# SoftDrink-SchematicFile.net
KiCad netlist of a schematic drawn in EAGLE
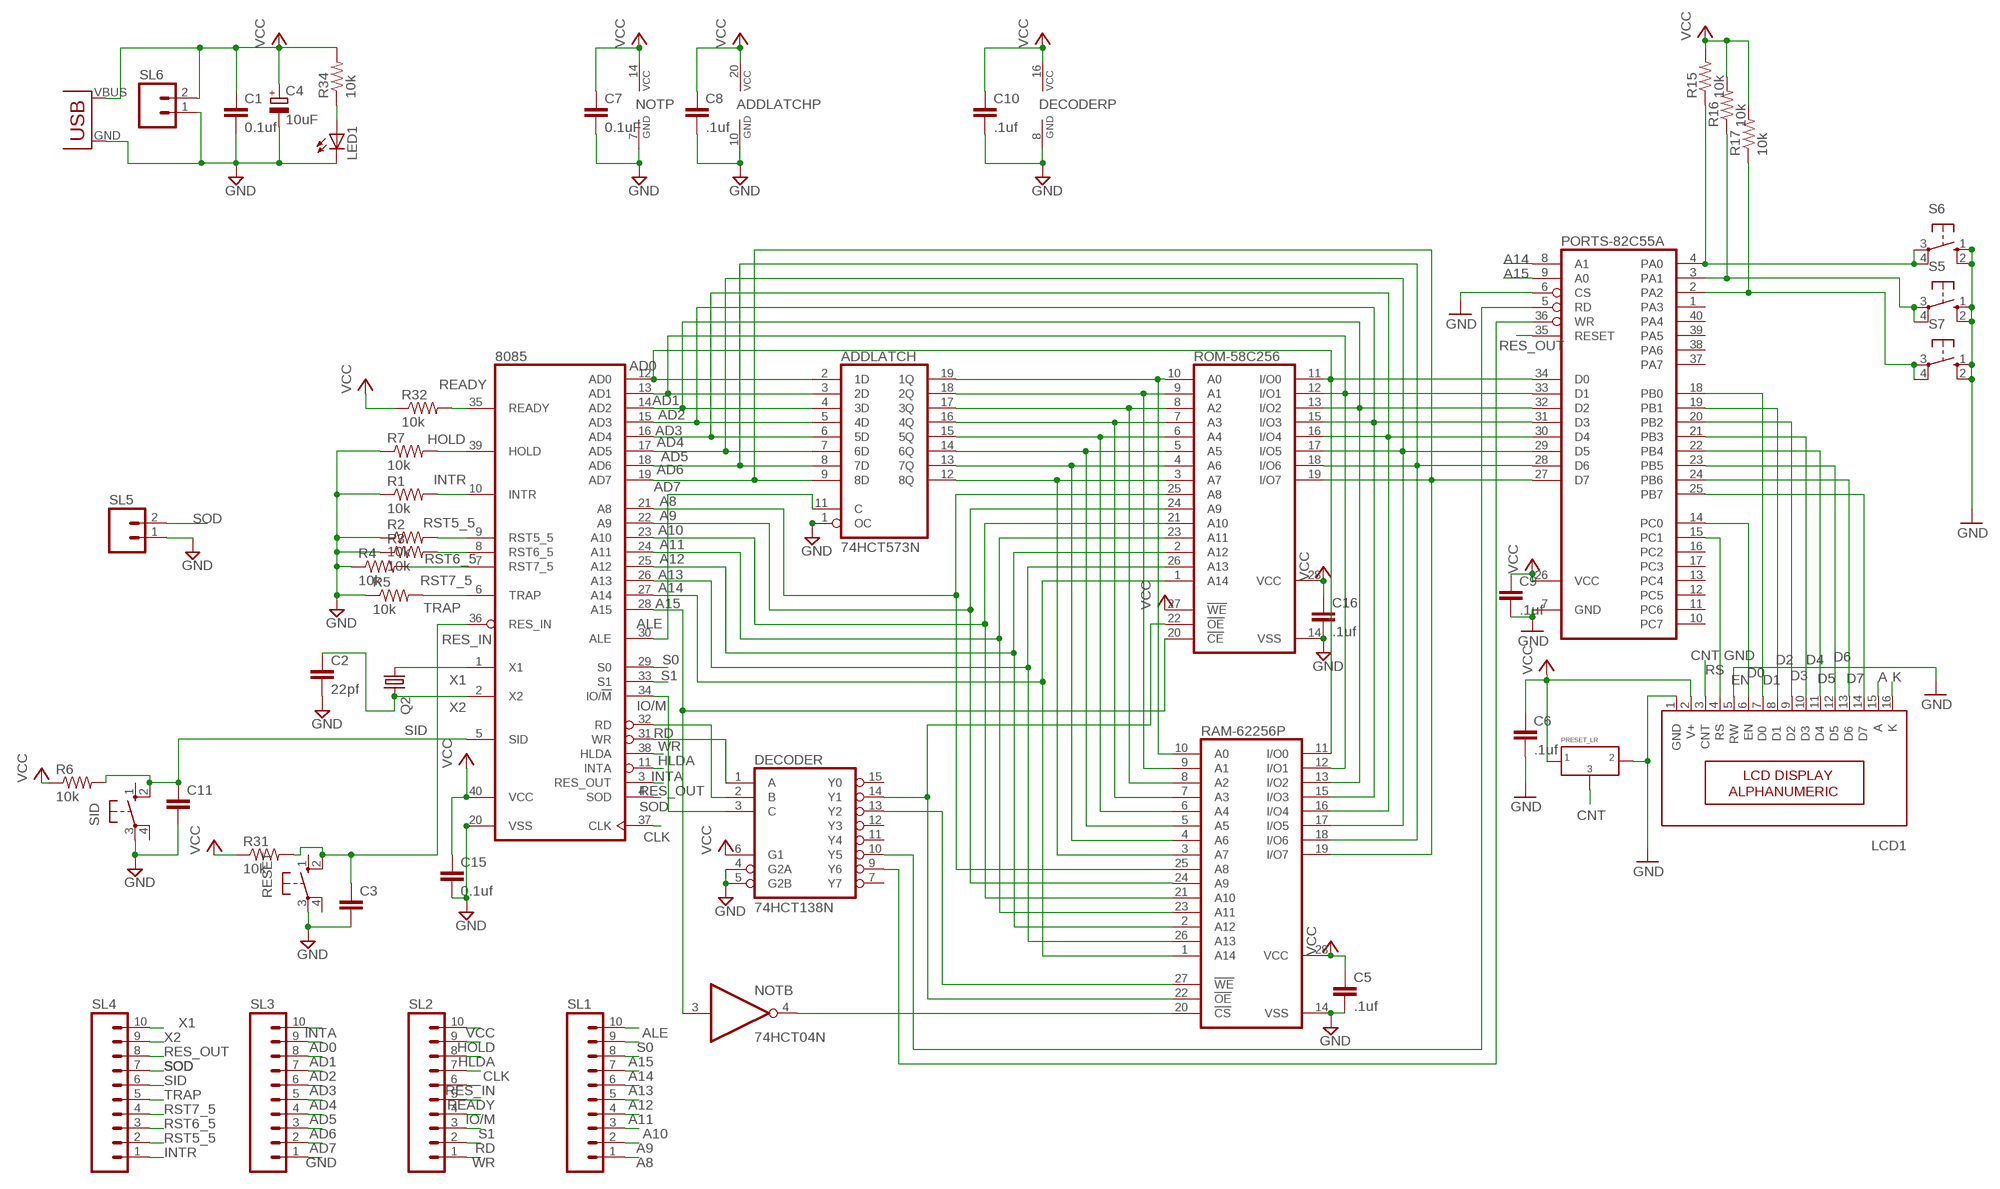
[diagram p0: schematic, sheet 1]

(export (version "E")
  (design (tool "Eeschema 10.0.6"))
  (components
    (comp (ref "8085")
      (value "8085")
      (footprint "eagle-import:DIL40")
      (libsource (lib "eagle-import") (part "8085"))
    )
    (comp (ref "ADDLATCH")
      (value "74HCT573N")
      (footprint "eagle-import:DIL20")
      (libsource (lib "eagle-import") (part "74573NHCT"))
    )
    (comp (ref "C1")
      (value "0.1uf")
      (footprint "eagle-import:C025-024X044")
      (libsource (lib "eagle-import") (part "C-EU025-024X044"))
    )
    (comp (ref "C2")
      (value "22pf")
      (footprint "eagle-import:C025-024X044")
      (libsource (lib "eagle-import") (part "C-EU025-024X044"))
    )
    (comp (ref "C3")
      (value "C-EU025-025X050")
      (footprint "eagle-import:C025-025X050")
      (libsource (lib "eagle-import") (part "C-EU025-025X050"))
    )
    (comp (ref "C4")
      (value "10uF")
      (footprint "eagle-import:E5-8,5")
      (libsource (lib "eagle-import") (part "CPOL-EUE5-8.5"))
    )
    (comp (ref "C5")
      (value ".1uf")
      (footprint "eagle-import:C025-024X044")
      (libsource (lib "eagle-import") (part "C-EU025-024X044"))
    )
    (comp (ref "C6")
      (value ".1uf")
      (footprint "eagle-import:C025-024X044")
      (libsource (lib "eagle-import") (part "C-EU025-024X044"))
    )
    (comp (ref "C7")
      (value "0.1uF")
      (footprint "eagle-import:C025-024X044")
      (libsource (lib "eagle-import") (part "C-EU025-024X044"))
    )
    (comp (ref "C8")
      (value ".1uf")
      (footprint "eagle-import:C025-024X044")
      (libsource (lib "eagle-import") (part "C-EU025-024X044"))
    )
    (comp (ref "C9")
      (value ".1uf")
      (footprint "eagle-import:C025-024X044")
      (libsource (lib "eagle-import") (part "C-EU025-024X044"))
    )
    (comp (ref "C10")
      (value ".1uf")
      (footprint "eagle-import:C025-024X044")
      (libsource (lib "eagle-import") (part "C-EU025-024X044"))
    )
    (comp (ref "C11")
      (value "C-EU025-025X050")
      (footprint "eagle-import:C025-025X050")
      (libsource (lib "eagle-import") (part "C-EU025-025X050"))
    )
    (comp (ref "C15")
      (value "0.1uf")
      (footprint "eagle-import:C025-024X044")
      (libsource (lib "eagle-import") (part "C-EU025-024X044"))
    )
    (comp (ref "C16")
      (value ".1uf")
      (footprint "eagle-import:C025-024X044")
      (libsource (lib "eagle-import") (part "C-EU025-024X044"))
    )
    (comp (ref "DECODER")
      (value "74HCT138N")
      (footprint "eagle-import:DIL16")
      (libsource (lib "eagle-import") (part "74138NHCT"))
    )
    (comp (ref "LCD1")
      (value "16X2LCD")
      (footprint "eagle-import:16X2_LCD")
      (libsource (lib "eagle-import") (part "16X2LCD"))
    )
    (comp (ref "LED1")
      (value "LED5MM")
      (footprint "eagle-import:LED5MM")
      (libsource (lib "eagle-import") (part "LED5MM"))
    )
    (comp (ref "NOT")
      (value "74HCT04N")
      (footprint "eagle-import:DIL14")
      (libsource (lib "eagle-import") (part "7404NHCT"))
    )
    (comp (ref "PORTS-82C55A")
      (value "82C55A")
      (footprint "eagle-import:DIL40")
      (fields (field (name "MF") "INTERSIL") (field (name "MPN") "IP82C55AZ"))
      (libsource (lib "eagle-import") (part "82C55A"))
    )
    (comp (ref "Q2")
      (value "CRYSTALHC49US")
      (footprint "eagle-import:HC49US")
      (libsource (lib "eagle-import") (part "CRYSTALHC49US"))
    )
    (comp (ref "R1")
      (value "10k")
      (footprint "eagle-import:0207_7")
      (libsource (lib "eagle-import") (part "R-US_0207/7"))
    )
    (comp (ref "R2")
      (value "10k")
      (footprint "eagle-import:0207_7")
      (libsource (lib "eagle-import") (part "R-US_0207/7"))
    )
    (comp (ref "R3")
      (value "10k")
      (footprint "eagle-import:0207_7")
      (libsource (lib "eagle-import") (part "R-US_0207/7"))
    )
    (comp (ref "R4")
      (value "10k")
      (footprint "eagle-import:0207_7")
      (libsource (lib "eagle-import") (part "R-US_0207/7"))
    )
    (comp (ref "R5")
      (value "10k")
      (footprint "eagle-import:0207_7")
      (libsource (lib "eagle-import") (part "R-US_0207/7"))
    )
    (comp (ref "R6")
      (value "10k")
      (footprint "eagle-import:0207_7")
      (libsource (lib "eagle-import") (part "R-US_0207/7"))
    )
    (comp (ref "R7")
      (value "10k")
      (footprint "eagle-import:0207_7")
      (libsource (lib "eagle-import") (part "R-US_0207/7"))
    )
    (comp (ref "R15")
      (value "10k")
      (footprint "eagle-import:0207_7")
      (libsource (lib "eagle-import") (part "R-US_0207/7"))
    )
    (comp (ref "R16")
      (value "10k")
      (footprint "eagle-import:0207_7")
      (libsource (lib "eagle-import") (part "R-US_0207/7"))
    )
    (comp (ref "R17")
      (value "10k")
      (footprint "eagle-import:0207_7")
      (libsource (lib "eagle-import") (part "R-US_0207/7"))
    )
    (comp (ref "R31")
      (value "10k")
      (footprint "eagle-import:0207_7")
      (libsource (lib "eagle-import") (part "R-US_0207/7"))
    )
    (comp (ref "R32")
      (value "10k")
      (footprint "eagle-import:0207_7")
      (libsource (lib "eagle-import") (part "R-US_0207/7"))
    )
    (comp (ref "R34")
      (value "10k")
      (footprint "eagle-import:0207_7")
      (libsource (lib "eagle-import") (part "R-US_0207/7"))
    )
    (comp (ref "RAM-62256P")
      (value "62256P")
      (footprint "eagle-import:DIL28-6")
      (libsource (lib "eagle-import") (part "62256P"))
    )
    (comp (ref "RESET")
      (value "10-XX")
      (footprint "eagle-import:B3F-10XX")
      (libsource (lib "eagle-import") (part "10-XX"))
    )
    (comp (ref "ROM-58C256")
      (value "58C256P")
      (footprint "eagle-import:DIL28-6")
      (fields (field (name "MPN") "HN58C256AP85E"))
      (libsource (lib "eagle-import") (part "58C256P"))
    )
    (comp (ref "S5")
      (value "10-XX")
      (footprint "eagle-import:B3F-10XX")
      (libsource (lib "eagle-import") (part "CEDTv79_10-XX"))
    )
    (comp (ref "S6")
      (value "10-XX")
      (footprint "eagle-import:B3F-10XX")
      (libsource (lib "eagle-import") (part "CEDTv79_10-XX"))
    )
    (comp (ref "S7")
      (value "10-XX")
      (footprint "eagle-import:B3F-10XX")
      (libsource (lib "eagle-import") (part "CEDTv79_10-XX"))
    )
    (comp (ref "SID")
      (value "10-XX")
      (footprint "eagle-import:B3F-10XX")
      (libsource (lib "eagle-import") (part "10-XX"))
    )
    (comp (ref "SL1")
      (value "M10")
      (footprint "eagle-import:10P")
      (libsource (lib "eagle-import") (part "M10"))
    )
    (comp (ref "SL2")
      (value "M10")
      (footprint "eagle-import:10P")
      (libsource (lib "eagle-import") (part "M10"))
    )
    (comp (ref "SL3")
      (value "M10")
      (footprint "eagle-import:10P")
      (libsource (lib "eagle-import") (part "M10"))
    )
    (comp (ref "SL4")
      (value "M10")
      (footprint "eagle-import:10P")
      (libsource (lib "eagle-import") (part "M10"))
    )
    (comp (ref "SL5")
      (value "M02")
      (footprint "eagle-import:02P")
      (libsource (lib "eagle-import") (part "M02"))
    )
    (comp (ref "SL6")
      (value "M02")
      (footprint "eagle-import:02P")
      (libsource (lib "eagle-import") (part "M02"))
    )
    (comp (ref "U$2")
      (value "USB(POWER)")
      (footprint "eagle-import:USB(POWER)")
      (libsource (lib "eagle-import") (part "USB(POWER)"))
    )
    (comp (ref "U$3")
      (value "PRESET_LR")
      (footprint "eagle-import:PRESET_LR")
      (libsource (lib "eagle-import") (part "PRESET_LR"))
    )
  )
  (nets
    (net (code "1") (name "/A") (class "Default")
      (node (ref "LCD1") (pin "15") (pinfunction "A_15") (pintype "bidirectional"))
    )
    (net (code "2") (name "/A8") (class "Default")
      (node (ref "8085") (pin "21") (pinfunction "A8_21") (pintype "output"))
      (node (ref "RAM-62256P") (pin "25") (pinfunction "A8_25") (pintype "input"))
      (node (ref "ROM-58C256") (pin "25") (pinfunction "A8_25") (pintype "input"))
      (node (ref "SL1") (pin "1") (pinfunction "1_1") (pintype "passive"))
    )
    (net (code "3") (name "/A9") (class "Default")
      (node (ref "8085") (pin "22") (pinfunction "A9_22") (pintype "output"))
      (node (ref "RAM-62256P") (pin "24") (pinfunction "A9_24") (pintype "input"))
      (node (ref "ROM-58C256") (pin "24") (pinfunction "A9_24") (pintype "input"))
      (node (ref "SL1") (pin "2") (pinfunction "2_2") (pintype "passive"))
    )
    (net (code "4") (name "/A10") (class "Default")
      (node (ref "8085") (pin "23") (pinfunction "A10_23") (pintype "output"))
      (node (ref "RAM-62256P") (pin "21") (pinfunction "A10_21") (pintype "input"))
      (node (ref "ROM-58C256") (pin "21") (pinfunction "A10_21") (pintype "input"))
      (node (ref "SL1") (pin "3") (pinfunction "3_3") (pintype "passive"))
    )
    (net (code "5") (name "/A11") (class "Default")
      (node (ref "8085") (pin "24") (pinfunction "A11_24") (pintype "output"))
      (node (ref "RAM-62256P") (pin "23") (pinfunction "A11_23") (pintype "input"))
      (node (ref "ROM-58C256") (pin "23") (pinfunction "A11_23") (pintype "input"))
      (node (ref "SL1") (pin "4") (pinfunction "4_4") (pintype "passive"))
    )
    (net (code "6") (name "/A12") (class "Default")
      (node (ref "8085") (pin "25") (pinfunction "A12_25") (pintype "output"))
      (node (ref "RAM-62256P") (pin "2") (pinfunction "A12_2") (pintype "input"))
      (node (ref "ROM-58C256") (pin "2") (pinfunction "A12_2") (pintype "input"))
      (node (ref "SL1") (pin "5") (pinfunction "5_5") (pintype "passive"))
    )
    (net (code "7") (name "/A13") (class "Default")
      (node (ref "8085") (pin "26") (pinfunction "A13_26") (pintype "output"))
      (node (ref "RAM-62256P") (pin "26") (pinfunction "A13_26") (pintype "input"))
      (node (ref "ROM-58C256") (pin "26") (pinfunction "A13_26") (pintype "input"))
      (node (ref "SL1") (pin "6") (pinfunction "6_6") (pintype "passive"))
    )
    (net (code "8") (name "/A14") (class "Default")
      (node (ref "8085") (pin "27") (pinfunction "A14_27") (pintype "output"))
      (node (ref "PORTS-82C55A") (pin "8") (pinfunction "A1_8") (pintype "input"))
      (node (ref "RAM-62256P") (pin "1") (pinfunction "A14_1") (pintype "input"))
      (node (ref "ROM-58C256") (pin "1") (pinfunction "A14_1") (pintype "input"))
      (node (ref "SL1") (pin "7") (pinfunction "7_7") (pintype "passive"))
    )
    (net (code "9") (name "/A15") (class "Default")
      (node (ref "8085") (pin "28") (pinfunction "A15_28") (pintype "output"))
      (node (ref "NOT") (pin "3") (pinfunction "I_3") (pintype "input"))
      (node (ref "PORTS-82C55A") (pin "9") (pinfunction "A0_9") (pintype "input"))
      (node (ref "ROM-58C256") (pin "20") (pinfunction "~{CE}_20") (pintype "input"))
      (node (ref "SL1") (pin "8") (pinfunction "8_8") (pintype "passive"))
    )
    (net (code "10") (name "/AD0") (class "Default")
      (node (ref "8085") (pin "12") (pinfunction "AD0_12") (pintype "bidirectional"))
      (node (ref "ADDLATCH") (pin "2") (pinfunction "1D_2") (pintype "input"))
      (node (ref "PORTS-82C55A") (pin "34") (pinfunction "D0_34") (pintype "bidirectional"))
      (node (ref "RAM-62256P") (pin "11") (pinfunction "I/O0_11") (pintype "bidirectional"))
      (node (ref "ROM-58C256") (pin "11") (pinfunction "I/O0_11") (pintype "tri_state"))
      (node (ref "SL3") (pin "9") (pinfunction "9_9") (pintype "passive"))
    )
    (net (code "11") (name "/AD1") (class "Default")
      (node (ref "8085") (pin "13") (pinfunction "AD1_13") (pintype "bidirectional"))
      (node (ref "ADDLATCH") (pin "3") (pinfunction "2D_3") (pintype "input"))
      (node (ref "PORTS-82C55A") (pin "33") (pinfunction "D1_33") (pintype "bidirectional"))
      (node (ref "RAM-62256P") (pin "12") (pinfunction "I/O1_12") (pintype "bidirectional"))
      (node (ref "ROM-58C256") (pin "12") (pinfunction "I/O1_12") (pintype "tri_state"))
      (node (ref "SL3") (pin "8") (pinfunction "8_8") (pintype "passive"))
    )
    (net (code "12") (name "/AD2") (class "Default")
      (node (ref "8085") (pin "14") (pinfunction "AD2_14") (pintype "bidirectional"))
      (node (ref "ADDLATCH") (pin "4") (pinfunction "3D_4") (pintype "input"))
      (node (ref "PORTS-82C55A") (pin "32") (pinfunction "D2_32") (pintype "bidirectional"))
      (node (ref "RAM-62256P") (pin "13") (pinfunction "I/O2_13") (pintype "bidirectional"))
      (node (ref "ROM-58C256") (pin "13") (pinfunction "I/O2_13") (pintype "tri_state"))
      (node (ref "SL3") (pin "7") (pinfunction "7_7") (pintype "passive"))
    )
    (net (code "13") (name "/AD3") (class "Default")
      (node (ref "8085") (pin "15") (pinfunction "AD3_15") (pintype "bidirectional"))
      (node (ref "ADDLATCH") (pin "5") (pinfunction "4D_5") (pintype "input"))
      (node (ref "PORTS-82C55A") (pin "31") (pinfunction "D3_31") (pintype "bidirectional"))
      (node (ref "RAM-62256P") (pin "15") (pinfunction "I/O3_15") (pintype "bidirectional"))
      (node (ref "ROM-58C256") (pin "15") (pinfunction "I/O3_15") (pintype "tri_state"))
      (node (ref "SL3") (pin "6") (pinfunction "6_6") (pintype "passive"))
    )
    (net (code "14") (name "/AD4") (class "Default")
      (node (ref "8085") (pin "16") (pinfunction "AD4_16") (pintype "bidirectional"))
      (node (ref "ADDLATCH") (pin "6") (pinfunction "5D_6") (pintype "input"))
      (node (ref "PORTS-82C55A") (pin "30") (pinfunction "D4_30") (pintype "bidirectional"))
      (node (ref "RAM-62256P") (pin "16") (pinfunction "I/O4_16") (pintype "bidirectional"))
      (node (ref "ROM-58C256") (pin "16") (pinfunction "I/O4_16") (pintype "tri_state"))
      (node (ref "SL3") (pin "5") (pinfunction "5_5") (pintype "passive"))
    )
    (net (code "15") (name "/AD5") (class "Default")
      (node (ref "8085") (pin "17") (pinfunction "AD5_17") (pintype "bidirectional"))
      (node (ref "ADDLATCH") (pin "7") (pinfunction "6D_7") (pintype "input"))
      (node (ref "PORTS-82C55A") (pin "29") (pinfunction "D5_29") (pintype "bidirectional"))
      (node (ref "RAM-62256P") (pin "17") (pinfunction "I/O5_17") (pintype "bidirectional"))
      (node (ref "ROM-58C256") (pin "17") (pinfunction "I/O5_17") (pintype "tri_state"))
      (node (ref "SL3") (pin "4") (pinfunction "4_4") (pintype "passive"))
    )
    (net (code "16") (name "/AD6") (class "Default")
      (node (ref "8085") (pin "18") (pinfunction "AD6_18") (pintype "bidirectional"))
      (node (ref "ADDLATCH") (pin "8") (pinfunction "7D_8") (pintype "input"))
      (node (ref "PORTS-82C55A") (pin "28") (pinfunction "D6_28") (pintype "bidirectional"))
      (node (ref "RAM-62256P") (pin "18") (pinfunction "I/O6_18") (pintype "bidirectional"))
      (node (ref "ROM-58C256") (pin "18") (pinfunction "I/O6_18") (pintype "tri_state"))
      (node (ref "SL3") (pin "3") (pinfunction "3_3") (pintype "passive"))
    )
    (net (code "17") (name "/AD7") (class "Default")
      (node (ref "8085") (pin "19") (pinfunction "AD7_19") (pintype "bidirectional"))
      (node (ref "ADDLATCH") (pin "9") (pinfunction "8D_9") (pintype "input"))
      (node (ref "PORTS-82C55A") (pin "27") (pinfunction "D7_27") (pintype "bidirectional"))
      (node (ref "RAM-62256P") (pin "19") (pinfunction "I/O7_19") (pintype "bidirectional"))
      (node (ref "ROM-58C256") (pin "19") (pinfunction "I/O7_19") (pintype "tri_state"))
      (node (ref "SL3") (pin "2") (pinfunction "2_2") (pintype "passive"))
    )
    (net (code "18") (name "/ALE") (class "Default")
      (node (ref "8085") (pin "30") (pinfunction "ALE_30") (pintype "output"))
      (node (ref "ADDLATCH") (pin "11") (pinfunction "C_11") (pintype "input"))
      (node (ref "SL1") (pin "10") (pinfunction "10_10") (pintype "passive"))
    )
    (net (code "19") (name "/CLK") (class "Default")
      (node (ref "8085") (pin "37") (pinfunction "CLK_37") (pintype "output"))
      (node (ref "SL2") (pin "7") (pinfunction "7_7") (pintype "passive"))
    )
    (net (code "20") (name "/CNT") (class "Default")
      (node (ref "LCD1") (pin "3") (pinfunction "CNT_3") (pintype "bidirectional"))
      (node (ref "U$3") (pin "P$3") (pinfunction "3_P$3") (pintype "passive"))
    )
    (net (code "21") (name "/D0") (class "Default")
      (node (ref "LCD1") (pin "7") (pinfunction "D0_7") (pintype "bidirectional"))
      (node (ref "PORTS-82C55A") (pin "18") (pinfunction "PB0_18") (pintype "bidirectional"))
    )
    (net (code "22") (name "/D1") (class "Default")
      (node (ref "LCD1") (pin "8") (pinfunction "D1_8") (pintype "bidirectional"))
      (node (ref "PORTS-82C55A") (pin "19") (pinfunction "PB1_19") (pintype "bidirectional"))
    )
    (net (code "23") (name "/D2") (class "Default")
      (node (ref "LCD1") (pin "9") (pinfunction "D2_9") (pintype "bidirectional"))
      (node (ref "PORTS-82C55A") (pin "20") (pinfunction "PB2_20") (pintype "bidirectional"))
    )
    (net (code "24") (name "/D3") (class "Default")
      (node (ref "LCD1") (pin "10") (pinfunction "D3_10") (pintype "bidirectional"))
      (node (ref "PORTS-82C55A") (pin "21") (pinfunction "PB3_21") (pintype "bidirectional"))
    )
    (net (code "25") (name "/D4") (class "Default")
      (node (ref "LCD1") (pin "11") (pinfunction "D4_11") (pintype "bidirectional"))
      (node (ref "PORTS-82C55A") (pin "22") (pinfunction "PB4_22") (pintype "bidirectional"))
    )
    (net (code "26") (name "/D5") (class "Default")
      (node (ref "LCD1") (pin "12") (pinfunction "D5_12") (pintype "bidirectional"))
      (node (ref "PORTS-82C55A") (pin "23") (pinfunction "PB5_23") (pintype "bidirectional"))
    )
    (net (code "27") (name "/D6") (class "Default")
      (node (ref "LCD1") (pin "13") (pinfunction "D6_13") (pintype "bidirectional"))
      (node (ref "PORTS-82C55A") (pin "24") (pinfunction "PB6_24") (pintype "bidirectional"))
    )
    (net (code "28") (name "/D7") (class "Default")
      (node (ref "LCD1") (pin "14") (pinfunction "D7_14") (pintype "bidirectional"))
      (node (ref "PORTS-82C55A") (pin "25") (pinfunction "PB7_25") (pintype "bidirectional"))
    )
    (net (code "29") (name "/EN") (class "Default")
      (node (ref "LCD1") (pin "6") (pinfunction "EN_6") (pintype "bidirectional"))
      (node (ref "PORTS-82C55A") (pin "14") (pinfunction "PC0_14") (pintype "bidirectional"))
    )
    (net (code "30") (name "/HLDA") (class "Default")
      (node (ref "8085") (pin "38") (pinfunction "HLDA_38") (pintype "output"))
      (node (ref "SL2") (pin "8") (pinfunction "8_8") (pintype "passive"))
    )
    (net (code "31") (name "/HOLD") (class "Default")
      (node (ref "8085") (pin "39") (pinfunction "HOLD_39") (pintype "input"))
      (node (ref "R7") (pin "2") (pinfunction "2_2") (pintype "passive"))
      (node (ref "SL2") (pin "9") (pinfunction "9_9") (pintype "passive"))
    )
    (net (code "32") (name "/INTA") (class "Default")
      (node (ref "8085") (pin "11") (pinfunction "INTA_11") (pintype "output"))
      (node (ref "SL3") (pin "10") (pinfunction "10_10") (pintype "passive"))
    )
    (net (code "33") (name "/INTR") (class "Default")
      (node (ref "8085") (pin "10") (pinfunction "INTR_10") (pintype "input"))
      (node (ref "R1") (pin "2") (pinfunction "2_2") (pintype "passive"))
      (node (ref "SL4") (pin "1") (pinfunction "1_1") (pintype "passive"))
    )
    (net (code "34") (name "/IO{slash}M") (class "Default")
      (node (ref "8085") (pin "34") (pinfunction "IO/~{M}_34") (pintype "output"))
      (node (ref "DECODER") (pin "3") (pinfunction "C_3") (pintype "input"))
      (node (ref "SL2") (pin "4") (pinfunction "4_4") (pintype "passive"))
    )
    (net (code "35") (name "/K") (class "Default")
      (node (ref "LCD1") (pin "16") (pinfunction "K_16") (pintype "bidirectional"))
    )
    (net (code "36") (name "/RD") (class "Default")
      (node (ref "8085") (pin "32") (pinfunction "RD_32") (pintype "output"))
      (node (ref "DECODER") (pin "2") (pinfunction "B_2") (pintype "input"))
      (node (ref "SL2") (pin "2") (pinfunction "2_2") (pintype "passive"))
    )
    (net (code "37") (name "/READY") (class "Default")
      (node (ref "8085") (pin "35") (pinfunction "READY_35") (pintype "input"))
      (node (ref "R32") (pin "2") (pinfunction "2_2") (pintype "passive"))
      (node (ref "SL2") (pin "5") (pinfunction "5_5") (pintype "passive"))
    )
    (net (code "38") (name "/RES_IN") (class "Default")
      (node (ref "8085") (pin "36") (pinfunction "RES_IN_36") (pintype "input"))
      (node (ref "C3") (pin "1") (pinfunction "1_1") (pintype "passive"))
      (node (ref "R31") (pin "2") (pinfunction "2_2") (pintype "passive"))
      (node (ref "RESET") (pin "2") (pinfunction "S1_2") (pintype "passive"))
      (node (ref "SL2") (pin "6") (pinfunction "6_6") (pintype "passive"))
    )
    (net (code "39") (name "/RES_OUT") (class "Default")
      (node (ref "8085") (pin "3") (pinfunction "RES_OUT_3") (pintype "output"))
      (node (ref "PORTS-82C55A") (pin "35") (pinfunction "RESET_35") (pintype "input"))
      (node (ref "SL4") (pin "8") (pinfunction "8_8") (pintype "passive"))
    )
    (net (code "40") (name "/RS") (class "Default")
      (node (ref "LCD1") (pin "4") (pinfunction "RS_4") (pintype "bidirectional"))
      (node (ref "PORTS-82C55A") (pin "15") (pinfunction "PC1_15") (pintype "bidirectional"))
    )
    (net (code "41") (name "/RST5_5") (class "Default")
      (node (ref "8085") (pin "9") (pinfunction "RST5_5_9") (pintype "input"))
      (node (ref "R2") (pin "2") (pinfunction "2_2") (pintype "passive"))
      (node (ref "SL4") (pin "2") (pinfunction "2_2") (pintype "passive"))
    )
    (net (code "42") (name "/RST6_5") (class "Default")
      (node (ref "8085") (pin "8") (pinfunction "RST6_5_8") (pintype "input"))
      (node (ref "R3") (pin "2") (pinfunction "2_2") (pintype "passive"))
      (node (ref "SL4") (pin "3") (pinfunction "3_3") (pintype "passive"))
    )
    (net (code "43") (name "/RST7_5") (class "Default")
      (node (ref "8085") (pin "7") (pinfunction "RST7_5_7") (pintype "input"))
      (node (ref "R4") (pin "2") (pinfunction "2_2") (pintype "passive"))
      (node (ref "SL4") (pin "4") (pinfunction "4_4") (pintype "passive"))
    )
    (net (code "44") (name "/S0") (class "Default")
      (node (ref "8085") (pin "29") (pinfunction "S0_29") (pintype "output"))
      (node (ref "SL1") (pin "9") (pinfunction "9_9") (pintype "passive"))
    )
    (net (code "45") (name "/S1") (class "Default")
      (node (ref "8085") (pin "33") (pinfunction "S1_33") (pintype "output"))
      (node (ref "SL2") (pin "3") (pinfunction "3_3") (pintype "passive"))
    )
    (net (code "46") (name "/SID") (class "Default")
      (node (ref "8085") (pin "5") (pinfunction "SID_5") (pintype "input"))
      (node (ref "C11") (pin "1") (pinfunction "1_1") (pintype "passive"))
      (node (ref "R6") (pin "2") (pinfunction "2_2") (pintype "passive"))
      (node (ref "SID") (pin "2") (pinfunction "S1_2") (pintype "passive"))
      (node (ref "SL4") (pin "6") (pinfunction "6_6") (pintype "passive"))
    )
    (net (code "47") (name "/SOD") (class "Default")
      (node (ref "8085") (pin "4") (pinfunction "SOD_4") (pintype "output"))
      (node (ref "SL4") (pin "7") (pinfunction "7_7") (pintype "passive"))
      (node (ref "SL5") (pin "2") (pinfunction "2_2") (pintype "passive"))
    )
    (net (code "48") (name "/TRAP") (class "Default")
      (node (ref "8085") (pin "6") (pinfunction "TRAP_6") (pintype "input"))
      (node (ref "R5") (pin "2") (pinfunction "2_2") (pintype "passive"))
      (node (ref "SL4") (pin "5") (pinfunction "5_5") (pintype "passive"))
    )
    (net (code "49") (name "/WR") (class "Default")
      (node (ref "8085") (pin "31") (pinfunction "WR_31") (pintype "output"))
      (node (ref "DECODER") (pin "1") (pinfunction "A_1") (pintype "input"))
      (node (ref "SL2") (pin "1") (pinfunction "1_1") (pintype "passive"))
    )
    (net (code "50") (name "/X1") (class "Default")
      (node (ref "8085") (pin "1") (pinfunction "X1_1") (pintype "input"))
      (node (ref "Q2") (pin "1") (pinfunction "1_1") (pintype "passive"))
      (node (ref "SL4") (pin "10") (pinfunction "10_10") (pintype "passive"))
    )
    (net (code "51") (name "/X2") (class "Default")
      (node (ref "8085") (pin "2") (pinfunction "X2_2") (pintype "input"))
      (node (ref "C2") (pin "1") (pinfunction "1_1") (pintype "passive"))
      (node (ref "Q2") (pin "2") (pinfunction "2_2") (pintype "passive"))
      (node (ref "SL4") (pin "9") (pinfunction "9_9") (pintype "passive"))
    )
    (net (code "52") (name "GND") (class "Default")
      (node (ref "8085") (pin "20") (pinfunction "VSS_20") (pintype "power_in"))
      (node (ref "ADDLATCH") (pin "1") (pinfunction "OC_1") (pintype "input"))
      (node (ref "ADDLATCH") (pin "10") (pinfunction "GND_10") (pintype "power_in"))
      (node (ref "C1") (pin "2") (pinfunction "2_2") (pintype "passive"))
      (node (ref "C10") (pin "2") (pinfunction "2_2") (pintype "passive"))
      (node (ref "C11") (pin "2") (pinfunction "2_2") (pintype "passive"))
      (node (ref "C15") (pin "2") (pinfunction "2_2") (pintype "passive"))
      (node (ref "C16") (pin "2") (pinfunction "2_2") (pintype "passive"))
      (node (ref "C2") (pin "2") (pinfunction "2_2") (pintype "passive"))
      (node (ref "C3") (pin "2") (pinfunction "2_2") (pintype "passive"))
      (node (ref "C4") (pin "-") (pinfunction "-_-") (pintype "passive"))
      (node (ref "C5") (pin "2") (pinfunction "2_2") (pintype "passive"))
      (node (ref "C6") (pin "2") (pinfunction "2_2") (pintype "passive"))
      (node (ref "C7") (pin "2") (pinfunction "2_2") (pintype "passive"))
      (node (ref "C8") (pin "2") (pinfunction "2_2") (pintype "passive"))
      (node (ref "C9") (pin "2") (pinfunction "2_2") (pintype "passive"))
      (node (ref "DECODER") (pin "4") (pinfunction "G2A_4") (pintype "input"))
      (node (ref "DECODER") (pin "5") (pinfunction "G2B_5") (pintype "input"))
      (node (ref "DECODER") (pin "8") (pinfunction "GND_8") (pintype "power_in"))
      (node (ref "LCD1") (pin "1") (pinfunction "GND_1") (pintype "bidirectional"))
      (node (ref "LCD1") (pin "5") (pinfunction "RW_5") (pintype "bidirectional"))
      (node (ref "LED1") (pin "K") (pinfunction "C_K") (pintype "passive"))
      (node (ref "NOT") (pin "7") (pinfunction "GND_7") (pintype "power_in"))
      (node (ref "PORTS-82C55A") (pin "6") (pinfunction "CS_6") (pintype "input"))
      (node (ref "PORTS-82C55A") (pin "7") (pinfunction "GND_7") (pintype "power_in"))
      (node (ref "R1") (pin "1") (pinfunction "1_1") (pintype "passive"))
      (node (ref "R2") (pin "1") (pinfunction "1_1") (pintype "passive"))
      (node (ref "R3") (pin "1") (pinfunction "1_1") (pintype "passive"))
      (node (ref "R4") (pin "1") (pinfunction "1_1") (pintype "passive"))
      (node (ref "R5") (pin "1") (pinfunction "1_1") (pintype "passive"))
      (node (ref "R7") (pin "1") (pinfunction "1_1") (pintype "passive"))
      (node (ref "RAM-62256P") (pin "14") (pinfunction "VSS_14") (pintype "power_in"))
      (node (ref "RESET") (pin "3") (pinfunction "P_3") (pintype "passive"))
      (node (ref "ROM-58C256") (pin "14") (pinfunction "VSS_14") (pintype "power_in"))
      (node (ref "S5") (pin "1") (pinfunction "S_1") (pintype "passive"))
      (node (ref "S5") (pin "2") (pinfunction "S1_2") (pintype "passive"))
      (node (ref "S6") (pin "1") (pinfunction "S_1") (pintype "passive"))
      (node (ref "S6") (pin "2") (pinfunction "S1_2") (pintype "passive"))
      (node (ref "S7") (pin "1") (pinfunction "S_1") (pintype "passive"))
      (node (ref "S7") (pin "2") (pinfunction "S1_2") (pintype "passive"))
      (node (ref "SID") (pin "3") (pinfunction "P_3") (pintype "passive"))
      (node (ref "SL3") (pin "1") (pinfunction "1_1") (pintype "passive"))
      (node (ref "SL5") (pin "1") (pinfunction "1_1") (pintype "passive"))
      (node (ref "SL6") (pin "1") (pinfunction "1_1") (pintype "passive"))
      (node (ref "U$2") (pin "GND") (pinfunction "GND_GND") (pintype "power_in"))
      (node (ref "U$3") (pin "P$2") (pinfunction "2_P$2") (pintype "passive"))
    )
    (net (code "53") (name "Net-(ADDLATCHA-1Q)") (class "Default")
      (node (ref "ADDLATCH") (pin "19") (pinfunction "1Q_19") (pintype "tri_state"))
      (node (ref "RAM-62256P") (pin "10") (pinfunction "A0_10") (pintype "input"))
      (node (ref "ROM-58C256") (pin "10") (pinfunction "A0_10") (pintype "input"))
    )
    (net (code "54") (name "Net-(ADDLATCHA-2Q)") (class "Default")
      (node (ref "ADDLATCH") (pin "18") (pinfunction "2Q_18") (pintype "tri_state"))
      (node (ref "RAM-62256P") (pin "9") (pinfunction "A1_9") (pintype "input"))
      (node (ref "ROM-58C256") (pin "9") (pinfunction "A1_9") (pintype "input"))
    )
    (net (code "55") (name "Net-(ADDLATCHA-3Q)") (class "Default")
      (node (ref "ADDLATCH") (pin "17") (pinfunction "3Q_17") (pintype "tri_state"))
      (node (ref "RAM-62256P") (pin "8") (pinfunction "A2_8") (pintype "input"))
      (node (ref "ROM-58C256") (pin "8") (pinfunction "A2_8") (pintype "input"))
    )
    (net (code "56") (name "Net-(ADDLATCHA-4Q)") (class "Default")
      (node (ref "ADDLATCH") (pin "16") (pinfunction "4Q_16") (pintype "tri_state"))
      (node (ref "RAM-62256P") (pin "7") (pinfunction "A3_7") (pintype "input"))
      (node (ref "ROM-58C256") (pin "7") (pinfunction "A3_7") (pintype "input"))
    )
    (net (code "57") (name "Net-(ADDLATCHA-5Q)") (class "Default")
      (node (ref "ADDLATCH") (pin "15") (pinfunction "5Q_15") (pintype "tri_state"))
      (node (ref "RAM-62256P") (pin "6") (pinfunction "A4_6") (pintype "input"))
      (node (ref "ROM-58C256") (pin "6") (pinfunction "A4_6") (pintype "input"))
    )
    (net (code "58") (name "Net-(ADDLATCHA-6Q)") (class "Default")
      (node (ref "ADDLATCH") (pin "14") (pinfunction "6Q_14") (pintype "tri_state"))
      (node (ref "RAM-62256P") (pin "5") (pinfunction "A5_5") (pintype "input"))
      (node (ref "ROM-58C256") (pin "5") (pinfunction "A5_5") (pintype "input"))
    )
    (net (code "59") (name "Net-(ADDLATCHA-7Q)") (class "Default")
      (node (ref "ADDLATCH") (pin "13") (pinfunction "7Q_13") (pintype "tri_state"))
      (node (ref "RAM-62256P") (pin "4") (pinfunction "A6_4") (pintype "input"))
      (node (ref "ROM-58C256") (pin "4") (pinfunction "A6_4") (pintype "input"))
    )
    (net (code "60") (name "Net-(ADDLATCHA-8Q)") (class "Default")
      (node (ref "ADDLATCH") (pin "12") (pinfunction "8Q_12") (pintype "tri_state"))
      (node (ref "RAM-62256P") (pin "3") (pinfunction "A7_3") (pintype "input"))
      (node (ref "ROM-58C256") (pin "3") (pinfunction "A7_3") (pintype "input"))
    )
    (net (code "61") (name "Net-(DECODERA-Y1)") (class "Default")
      (node (ref "DECODER") (pin "14") (pinfunction "Y1_14") (pintype "output"))
      (node (ref "RAM-62256P") (pin "22") (pinfunction "~{OE}_22") (pintype "input"))
      (node (ref "ROM-58C256") (pin "22") (pinfunction "~{OE}_22") (pintype "input"))
    )
    (net (code "62") (name "Net-(DECODERA-Y2)") (class "Default")
      (node (ref "DECODER") (pin "13") (pinfunction "Y2_13") (pintype "output"))
      (node (ref "RAM-62256P") (pin "27") (pinfunction "~{WE}_27") (pintype "input"))
    )
    (net (code "63") (name "Net-(DECODERA-Y5)") (class "Default")
      (node (ref "DECODER") (pin "10") (pinfunction "Y5_10") (pintype "output"))
      (node (ref "PORTS-82C55A") (pin "5") (pinfunction "RD_5") (pintype "input"))
    )
    (net (code "64") (name "Net-(DECODERA-Y6)") (class "Default")
      (node (ref "DECODER") (pin "9") (pinfunction "Y6_9") (pintype "output"))
      (node (ref "PORTS-82C55A") (pin "36") (pinfunction "WR_36") (pintype "input"))
    )
    (net (code "65") (name "Net-(LED1-PadA)") (class "Default")
      (node (ref "LED1") (pin "A") (pinfunction "A_A") (pintype "passive"))
      (node (ref "R34") (pin "1") (pinfunction "1_1") (pintype "passive"))
    )
    (net (code "66") (name "Net-(NOTB-O)") (class "Default")
      (node (ref "NOT") (pin "4") (pinfunction "O_4") (pintype "output"))
      (node (ref "RAM-62256P") (pin "20") (pinfunction "~{CS}_20") (pintype "input"))
    )
    (net (code "67") (name "Net-(PORTS-82C55A-PA0)") (class "Default")
      (node (ref "PORTS-82C55A") (pin "4") (pinfunction "PA0_4") (pintype "bidirectional"))
      (node (ref "R15") (pin "1") (pinfunction "1_1") (pintype "passive"))
      (node (ref "S6") (pin "3") (pinfunction "P_3") (pintype "passive"))
      (node (ref "S6") (pin "4") (pinfunction "P1_4") (pintype "passive"))
    )
    (net (code "68") (name "Net-(PORTS-82C55A-PA1)") (class "Default")
      (node (ref "PORTS-82C55A") (pin "3") (pinfunction "PA1_3") (pintype "bidirectional"))
      (node (ref "R16") (pin "1") (pinfunction "1_1") (pintype "passive"))
      (node (ref "S5") (pin "3") (pinfunction "P_3") (pintype "passive"))
      (node (ref "S5") (pin "4") (pinfunction "P1_4") (pintype "passive"))
    )
    (net (code "69") (name "Net-(PORTS-82C55A-PA2)") (class "Default")
      (node (ref "PORTS-82C55A") (pin "2") (pinfunction "PA2_2") (pintype "bidirectional"))
      (node (ref "R17") (pin "1") (pinfunction "1_1") (pintype "passive"))
      (node (ref "S7") (pin "3") (pinfunction "P_3") (pintype "passive"))
      (node (ref "S7") (pin "4") (pinfunction "P1_4") (pintype "passive"))
    )
    (net (code "70") (name "VCC") (class "Default")
      (node (ref "8085") (pin "40") (pinfunction "VCC_40") (pintype "power_in"))
      (node (ref "ADDLATCH") (pin "20") (pinfunction "VCC_20") (pintype "power_in"))
      (node (ref "C1") (pin "1") (pinfunction "1_1") (pintype "passive"))
      (node (ref "C10") (pin "1") (pinfunction "1_1") (pintype "passive"))
      (node (ref "C15") (pin "1") (pinfunction "1_1") (pintype "passive"))
      (node (ref "C16") (pin "1") (pinfunction "1_1") (pintype "passive"))
      (node (ref "C4") (pin "+") (pinfunction "+_+") (pintype "passive"))
      (node (ref "C5") (pin "1") (pinfunction "1_1") (pintype "passive"))
      (node (ref "C6") (pin "1") (pinfunction "1_1") (pintype "passive"))
      (node (ref "C7") (pin "1") (pinfunction "1_1") (pintype "passive"))
      (node (ref "C8") (pin "1") (pinfunction "1_1") (pintype "passive"))
      (node (ref "C9") (pin "1") (pinfunction "1_1") (pintype "passive"))
      (node (ref "DECODER") (pin "16") (pinfunction "VCC_16") (pintype "power_in"))
      (node (ref "DECODER") (pin "6") (pinfunction "G1_6") (pintype "input"))
      (node (ref "LCD1") (pin "2") (pinfunction "V+_2") (pintype "bidirectional"))
      (node (ref "NOT") (pin "14") (pinfunction "VCC_14") (pintype "power_in"))
      (node (ref "PORTS-82C55A") (pin "26") (pinfunction "VCC_26") (pintype "power_in"))
      (node (ref "R15") (pin "2") (pinfunction "2_2") (pintype "passive"))
      (node (ref "R16") (pin "2") (pinfunction "2_2") (pintype "passive"))
      (node (ref "R17") (pin "2") (pinfunction "2_2") (pintype "passive"))
      (node (ref "R31") (pin "1") (pinfunction "1_1") (pintype "passive"))
      (node (ref "R32") (pin "1") (pinfunction "1_1") (pintype "passive"))
      (node (ref "R34") (pin "2") (pinfunction "2_2") (pintype "passive"))
      (node (ref "R6") (pin "1") (pinfunction "1_1") (pintype "passive"))
      (node (ref "RAM-62256P") (pin "28") (pinfunction "VCC_28") (pintype "power_in"))
      (node (ref "ROM-58C256") (pin "27") (pinfunction "~{WE}_27") (pintype "input"))
      (node (ref "ROM-58C256") (pin "28") (pinfunction "VCC_28") (pintype "power_in"))
      (node (ref "SL2") (pin "10") (pinfunction "10_10") (pintype "passive"))
      (node (ref "SL6") (pin "2") (pinfunction "2_2") (pintype "passive"))
      (node (ref "U$2") (pin "VBUS") (pinfunction "VCC_VBUS") (pintype "power_in"))
      (node (ref "U$3") (pin "P$1") (pinfunction "1_P$1") (pintype "passive"))
    )
    (net (code "71") (name "unconnected-(DECODERA-Y0-Pad15)") (class "Default")
      (node (ref "DECODER") (pin "15") (pinfunction "Y0_15") (pintype "output"))
    )
    (net (code "72") (name "unconnected-(DECODERA-Y3-Pad12)") (class "Default")
      (node (ref "DECODER") (pin "12") (pinfunction "Y3_12") (pintype "output"))
    )
    (net (code "73") (name "unconnected-(DECODERA-Y4-Pad11)") (class "Default")
      (node (ref "DECODER") (pin "11") (pinfunction "Y4_11") (pintype "output"))
    )
    (net (code "74") (name "unconnected-(DECODERA-Y7-Pad7)") (class "Default")
      (node (ref "DECODER") (pin "7") (pinfunction "Y7_7") (pintype "output"))
    )
    (net (code "75") (name "unconnected-(PORTS-82C55A-PA3-Pad1)") (class "Default")
      (node (ref "PORTS-82C55A") (pin "1") (pinfunction "PA3_1") (pintype "bidirectional"))
    )
    (net (code "76") (name "unconnected-(PORTS-82C55A-PA4-Pad40)") (class "Default")
      (node (ref "PORTS-82C55A") (pin "40") (pinfunction "PA4_40") (pintype "bidirectional"))
    )
    (net (code "77") (name "unconnected-(PORTS-82C55A-PA5-Pad39)") (class "Default")
      (node (ref "PORTS-82C55A") (pin "39") (pinfunction "PA5_39") (pintype "bidirectional"))
    )
    (net (code "78") (name "unconnected-(PORTS-82C55A-PA6-Pad38)") (class "Default")
      (node (ref "PORTS-82C55A") (pin "38") (pinfunction "PA6_38") (pintype "bidirectional"))
    )
    (net (code "79") (name "unconnected-(PORTS-82C55A-PA7-Pad37)") (class "Default")
      (node (ref "PORTS-82C55A") (pin "37") (pinfunction "PA7_37") (pintype "bidirectional"))
    )
    (net (code "80") (name "unconnected-(PORTS-82C55A-PC2-Pad16)") (class "Default")
      (node (ref "PORTS-82C55A") (pin "16") (pinfunction "PC2_16") (pintype "bidirectional"))
    )
    (net (code "81") (name "unconnected-(PORTS-82C55A-PC3-Pad17)") (class "Default")
      (node (ref "PORTS-82C55A") (pin "17") (pinfunction "PC3_17") (pintype "bidirectional"))
    )
    (net (code "82") (name "unconnected-(PORTS-82C55A-PC4-Pad13)") (class "Default")
      (node (ref "PORTS-82C55A") (pin "13") (pinfunction "PC4_13") (pintype "bidirectional"))
    )
    (net (code "83") (name "unconnected-(PORTS-82C55A-PC5-Pad12)") (class "Default")
      (node (ref "PORTS-82C55A") (pin "12") (pinfunction "PC5_12") (pintype "bidirectional"))
    )
    (net (code "84") (name "unconnected-(PORTS-82C55A-PC6-Pad11)") (class "Default")
      (node (ref "PORTS-82C55A") (pin "11") (pinfunction "PC6_11") (pintype "bidirectional"))
    )
    (net (code "85") (name "unconnected-(PORTS-82C55A-PC7-Pad10)") (class "Default")
      (node (ref "PORTS-82C55A") (pin "10") (pinfunction "PC7_10") (pintype "bidirectional"))
    )
    (net (code "86") (name "unconnected-(RESET-P1-Pad4)") (class "Default")
      (node (ref "RESET") (pin "4") (pinfunction "P1_4") (pintype "passive"))
    )
    (net (code "87") (name "unconnected-(RESET-S-Pad1)") (class "Default")
      (node (ref "RESET") (pin "1") (pinfunction "S_1") (pintype "passive"))
    )
    (net (code "88") (name "unconnected-(SID-P1-Pad4)") (class "Default")
      (node (ref "SID") (pin "4") (pinfunction "P1_4") (pintype "passive"))
    )
    (net (code "89") (name "unconnected-(SID-S-Pad1)") (class "Default")
      (node (ref "SID") (pin "1") (pinfunction "S_1") (pintype "passive"))
    )
  )
)
